# VSSOP-10_Breakout_Board.net
KiCad netlist of a schematic drawn in EAGLE
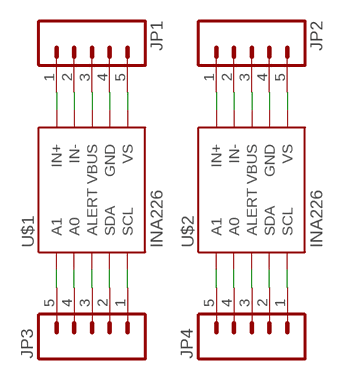
[diagram p0: schematic, sheet 1]

(export (version "E")
  (design (tool "Eeschema 10.0.6"))
  (components
    (comp (ref "JP1")
      (value "M05")
      (footprint "eagle-import:1X05")
      (libsource (lib "eagle-import") (part "M05"))
    )
    (comp (ref "JP2")
      (value "M05")
      (footprint "eagle-import:1X05")
      (libsource (lib "eagle-import") (part "M05"))
    )
    (comp (ref "JP3")
      (value "M05")
      (footprint "eagle-import:1X05")
      (libsource (lib "eagle-import") (part "M05"))
    )
    (comp (ref "JP4")
      (value "M05")
      (footprint "eagle-import:1X05")
      (libsource (lib "eagle-import") (part "M05"))
    )
    (comp (ref "U$1")
      (value "INA226")
      (footprint "eagle-import:VSSOP-10")
      (libsource (lib "eagle-import") (part "INA226"))
    )
    (comp (ref "U$2")
      (value "INA226")
      (footprint "eagle-import:VSSOP-10")
      (libsource (lib "eagle-import") (part "INA226"))
    )
  )
  (nets
    (net (code "1") (name "Net-(U$1-A0)") (class "Default")
      (node (ref "JP3") (pin "4") (pinfunction "4_4") (pintype "passive"))
      (node (ref "U$1") (pin "2") (pinfunction "A0_2") (pintype "passive"))
    )
    (net (code "2") (name "Net-(U$1-A1)") (class "Default")
      (node (ref "JP3") (pin "5") (pinfunction "5_5") (pintype "passive"))
      (node (ref "U$1") (pin "1") (pinfunction "A1_1") (pintype "passive"))
    )
    (net (code "3") (name "Net-(U$1-ALERT)") (class "Default")
      (node (ref "JP3") (pin "3") (pinfunction "3_3") (pintype "passive"))
      (node (ref "U$1") (pin "3") (pinfunction "ALERT_3") (pintype "passive"))
    )
    (net (code "4") (name "Net-(U$1-GND)") (class "Default")
      (node (ref "JP1") (pin "4") (pinfunction "4_4") (pintype "passive"))
      (node (ref "U$1") (pin "7") (pinfunction "GND_7") (pintype "passive"))
    )
    (net (code "5") (name "Net-(U$1-IN+)") (class "Default")
      (node (ref "JP1") (pin "1") (pinfunction "1_1") (pintype "passive"))
      (node (ref "U$1") (pin "10") (pinfunction "IN+_10") (pintype "passive"))
    )
    (net (code "6") (name "Net-(U$1-IN-)") (class "Default")
      (node (ref "JP1") (pin "2") (pinfunction "2_2") (pintype "passive"))
      (node (ref "U$1") (pin "9") (pinfunction "IN-_9") (pintype "passive"))
    )
    (net (code "7") (name "Net-(U$1-SCL)") (class "Default")
      (node (ref "JP3") (pin "1") (pinfunction "1_1") (pintype "passive"))
      (node (ref "U$1") (pin "5") (pinfunction "SCL_5") (pintype "passive"))
    )
    (net (code "8") (name "Net-(U$1-SDA)") (class "Default")
      (node (ref "JP3") (pin "2") (pinfunction "2_2") (pintype "passive"))
      (node (ref "U$1") (pin "4") (pinfunction "SDA_4") (pintype "passive"))
    )
    (net (code "9") (name "Net-(U$1-VBUS)") (class "Default")
      (node (ref "JP1") (pin "3") (pinfunction "3_3") (pintype "passive"))
      (node (ref "U$1") (pin "8") (pinfunction "VBUS_8") (pintype "passive"))
    )
    (net (code "10") (name "Net-(U$1-VS)") (class "Default")
      (node (ref "JP1") (pin "5") (pinfunction "5_5") (pintype "passive"))
      (node (ref "U$1") (pin "6") (pinfunction "VS_6") (pintype "passive"))
    )
    (net (code "11") (name "Net-(U$2-A0)") (class "Default")
      (node (ref "JP4") (pin "4") (pinfunction "4_4") (pintype "passive"))
      (node (ref "U$2") (pin "2") (pinfunction "A0_2") (pintype "passive"))
    )
    (net (code "12") (name "Net-(U$2-A1)") (class "Default")
      (node (ref "JP4") (pin "5") (pinfunction "5_5") (pintype "passive"))
      (node (ref "U$2") (pin "1") (pinfunction "A1_1") (pintype "passive"))
    )
    (net (code "13") (name "Net-(U$2-ALERT)") (class "Default")
      (node (ref "JP4") (pin "3") (pinfunction "3_3") (pintype "passive"))
      (node (ref "U$2") (pin "3") (pinfunction "ALERT_3") (pintype "passive"))
    )
    (net (code "14") (name "Net-(U$2-GND)") (class "Default")
      (node (ref "JP2") (pin "4") (pinfunction "4_4") (pintype "passive"))
      (node (ref "U$2") (pin "7") (pinfunction "GND_7") (pintype "passive"))
    )
    (net (code "15") (name "Net-(U$2-IN+)") (class "Default")
      (node (ref "JP2") (pin "1") (pinfunction "1_1") (pintype "passive"))
      (node (ref "U$2") (pin "10") (pinfunction "IN+_10") (pintype "passive"))
    )
    (net (code "16") (name "Net-(U$2-IN-)") (class "Default")
      (node (ref "JP2") (pin "2") (pinfunction "2_2") (pintype "passive"))
      (node (ref "U$2") (pin "9") (pinfunction "IN-_9") (pintype "passive"))
    )
    (net (code "17") (name "Net-(U$2-SCL)") (class "Default")
      (node (ref "JP4") (pin "1") (pinfunction "1_1") (pintype "passive"))
      (node (ref "U$2") (pin "5") (pinfunction "SCL_5") (pintype "passive"))
    )
    (net (code "18") (name "Net-(U$2-SDA)") (class "Default")
      (node (ref "JP4") (pin "2") (pinfunction "2_2") (pintype "passive"))
      (node (ref "U$2") (pin "4") (pinfunction "SDA_4") (pintype "passive"))
    )
    (net (code "19") (name "Net-(U$2-VBUS)") (class "Default")
      (node (ref "JP2") (pin "3") (pinfunction "3_3") (pintype "passive"))
      (node (ref "U$2") (pin "8") (pinfunction "VBUS_8") (pintype "passive"))
    )
    (net (code "20") (name "Net-(U$2-VS)") (class "Default")
      (node (ref "JP2") (pin "5") (pinfunction "5_5") (pintype "passive"))
      (node (ref "U$2") (pin "6") (pinfunction "VS_6") (pintype "passive"))
    )
  )
)
